# matts_pcb_schematic_v3.net
KiCad netlist of a schematic drawn in EAGLE
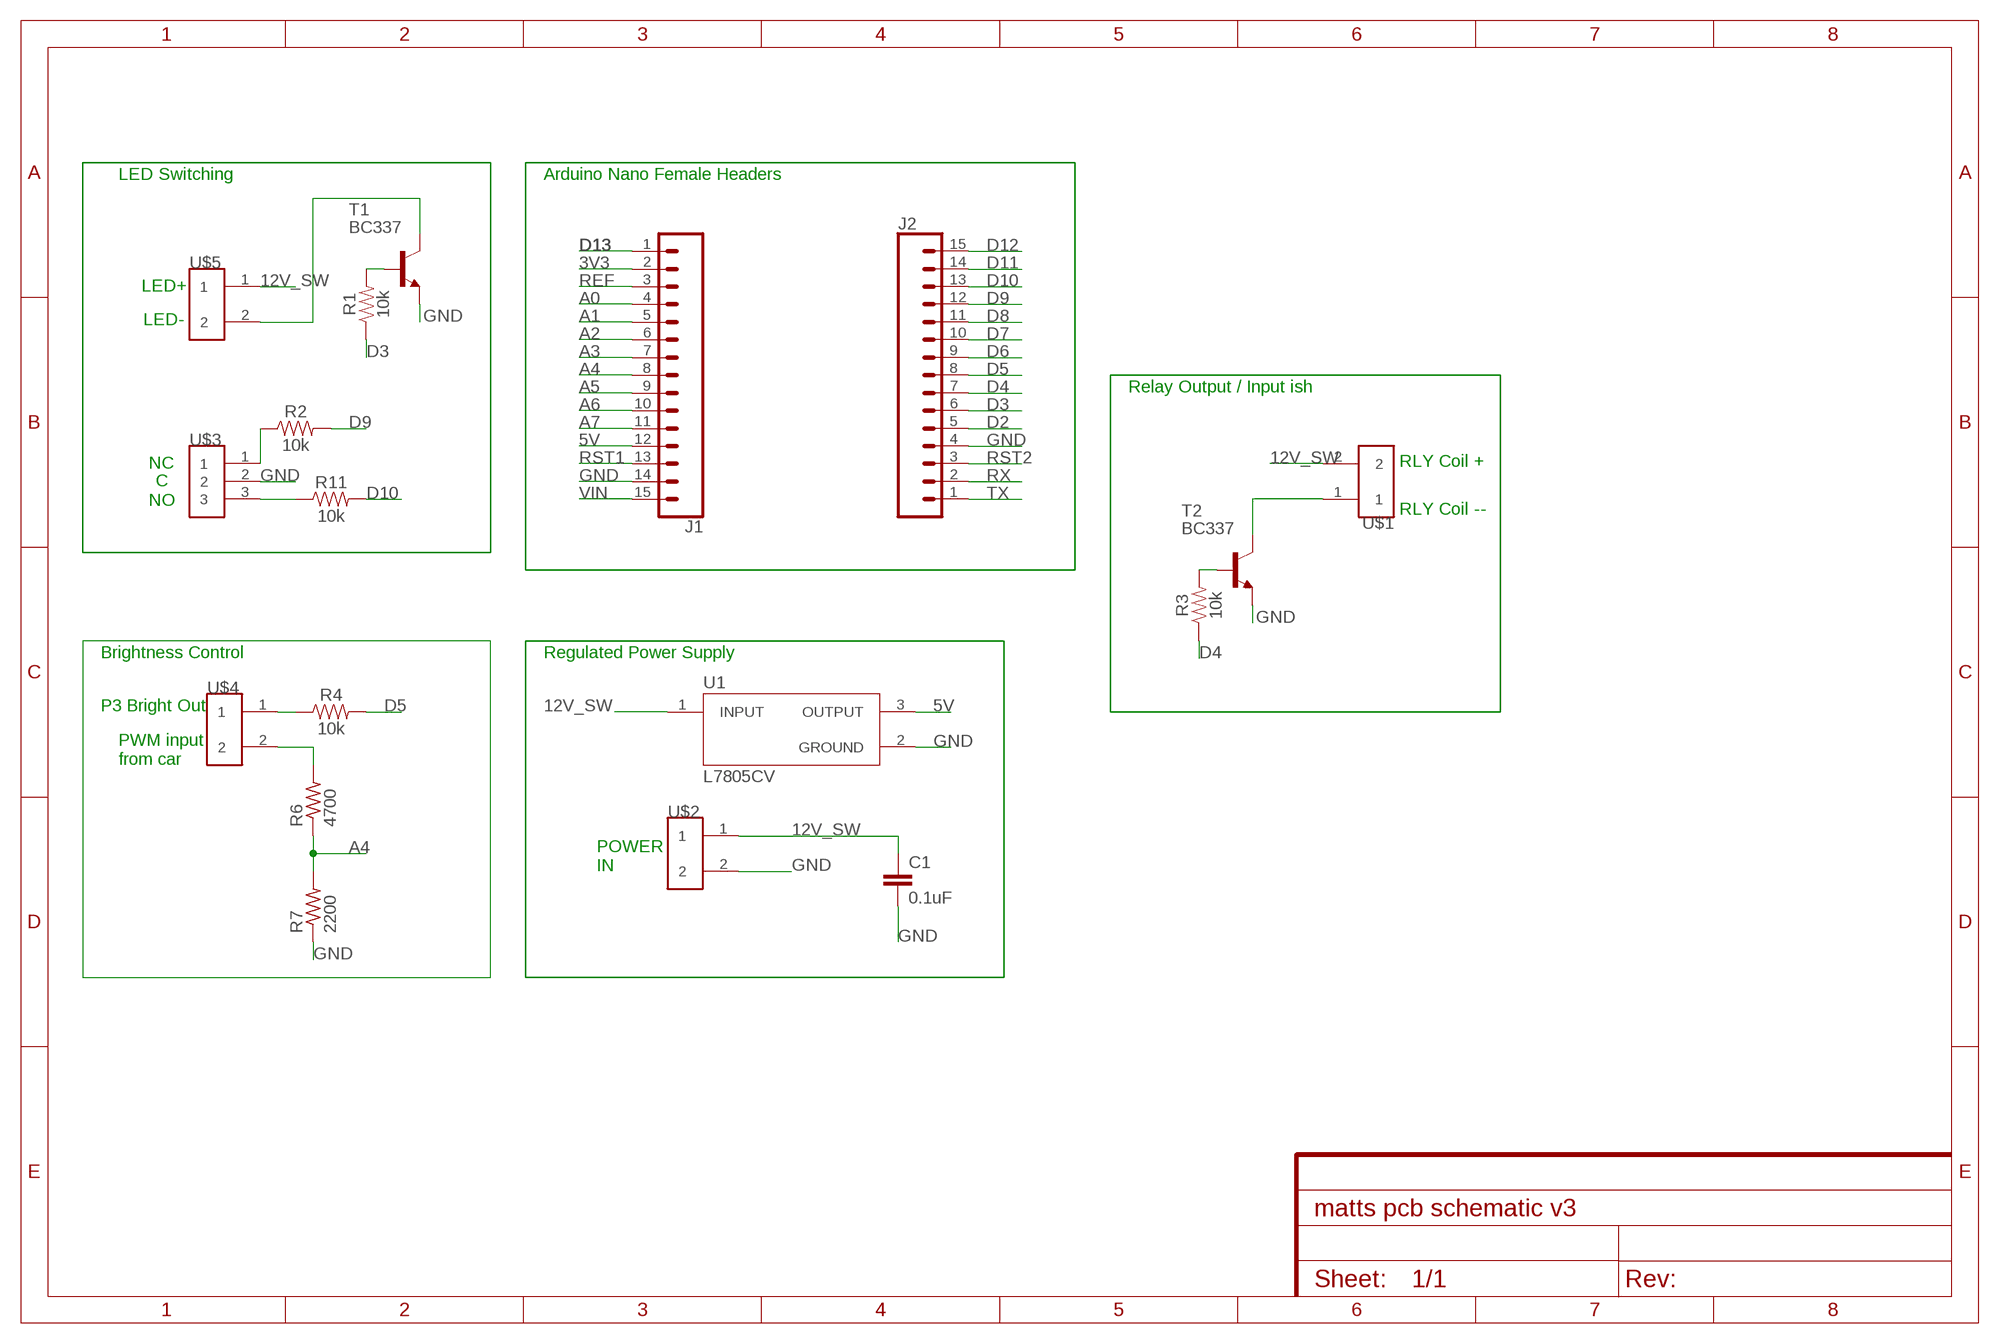
[diagram p0: schematic, sheet 1]

(export (version "E")
  (design (tool "Eeschema 10.0.6"))
  (components
    (comp (ref "C1")
      (value "0.1uF")
      (footprint "eagle-import:CAP-PTH-SMALL-KIT")
      (libsource (lib "eagle-import") (part "0.1UF-KIT-EZ-50V-20%"))
    )
    (comp (ref "J1")
      (value "CONN_15")
      (footprint "eagle-import:1X15")
      (libsource (lib "eagle-import") (part "CONN_15"))
    )
    (comp (ref "J2")
      (value "CONN_15")
      (footprint "eagle-import:1X15")
      (libsource (lib "eagle-import") (part "CONN_15"))
    )
    (comp (ref "R1")
      (value "10k")
      (footprint "eagle-import:AXIAL-0.3")
      (libsource (lib "eagle-import") (part "100KOHM-HORIZ-1/4W-1%"))
    )
    (comp (ref "R2")
      (value "10k")
      (footprint "eagle-import:AXIAL-0.3")
      (libsource (lib "eagle-import") (part "100KOHM-HORIZ-1/4W-1%"))
    )
    (comp (ref "R3")
      (value "10k")
      (footprint "eagle-import:AXIAL-0.3")
      (libsource (lib "eagle-import") (part "100KOHM-HORIZ-1/4W-1%"))
    )
    (comp (ref "R4")
      (value "10k")
      (footprint "eagle-import:AXIAL-0.3")
      (libsource (lib "eagle-import") (part "100KOHM-HORIZ-1/4W-1%"))
    )
    (comp (ref "R6")
      (value "4700")
      (footprint "eagle-import:0207_10")
      (libsource (lib "eagle-import") (part "R-US_0207/10"))
    )
    (comp (ref "R7")
      (value "2200")
      (footprint "eagle-import:0207_10")
      (libsource (lib "eagle-import") (part "R-US_0207/10"))
    )
    (comp (ref "R11")
      (value "10k")
      (footprint "eagle-import:AXIAL-0.3")
      (libsource (lib "eagle-import") (part "100KOHM-HORIZ-1/4W-1%"))
    )
    (comp (ref "T1")
      (value "BC337")
      (footprint "eagle-import:TO92")
      (libsource (lib "eagle-import") (part "BC337"))
    )
    (comp (ref "T2")
      (value "BC337")
      (footprint "eagle-import:TO92")
      (libsource (lib "eagle-import") (part "BC337"))
    )
    (comp (ref "U$1")
      (value "2PIN_0.2PITCH_SCREW_TERMINAL")
      (footprint "eagle-import:2PIN_0.2PITCH_SCREW_TERMINAL")
      (libsource (lib "eagle-import") (part "2PIN_0.2PITCH_SCREW_TERMINAL"))
    )
    (comp (ref "U$2")
      (value "2PIN_0.2PITCH_SCREW_TERMINAL")
      (footprint "eagle-import:2PIN_0.2PITCH_SCREW_TERMINAL")
      (libsource (lib "eagle-import") (part "2PIN_0.2PITCH_SCREW_TERMINAL"))
    )
    (comp (ref "U$3")
      (value "3PIN_0.2PITCH_SCREW_TERMINAL")
      (footprint "eagle-import:3PIN_0.2PITCH_SCREW_TERMINAL")
      (libsource (lib "eagle-import") (part "3PIN_0.2PITCH_SCREW_TERMINAL"))
    )
    (comp (ref "U$4")
      (value "2PIN_0.2PITCH_SCREW_TERMINAL")
      (footprint "eagle-import:2PIN_0.2PITCH_SCREW_TERMINAL")
      (libsource (lib "eagle-import") (part "2PIN_0.2PITCH_SCREW_TERMINAL"))
    )
    (comp (ref "U$5")
      (value "2PIN_0.2PITCH_SCREW_TERMINAL")
      (footprint "eagle-import:2PIN_0.2PITCH_SCREW_TERMINAL")
      (libsource (lib "eagle-import") (part "2PIN_0.2PITCH_SCREW_TERMINAL"))
    )
    (comp (ref "U1")
      (value "L7805CV")
      (footprint "eagle-import:TO255P1040X460X1968-3")
      (fields (field (name "MF") "STMicroelectronics"))
      (libsource (lib "eagle-import") (part "L7805CV"))
    )
  )
  (nets
    (net (code "1") (name "/3V3") (class "Default")
      (node (ref "J1") (pin "2") (pinfunction "2_2") (pintype "passive"))
    )
    (net (code "2") (name "/5V") (class "Default")
      (node (ref "J1") (pin "12") (pinfunction "12_12") (pintype "passive"))
      (node (ref "U1") (pin "3") (pinfunction "OUTPUT_3") (pintype "output"))
    )
    (net (code "3") (name "/12V_SW") (class "Default")
      (node (ref "C1") (pin "1") (pinfunction "1_1") (pintype "passive"))
      (node (ref "U$1") (pin "2") (pinfunction "2_2") (pintype "bidirectional"))
      (node (ref "U$2") (pin "1") (pinfunction "1_1") (pintype "bidirectional"))
      (node (ref "U$5") (pin "1") (pinfunction "1_1") (pintype "bidirectional"))
      (node (ref "U1") (pin "1") (pinfunction "INPUT_1") (pintype "input"))
    )
    (net (code "4") (name "/A0") (class "Default")
      (node (ref "J1") (pin "4") (pinfunction "4_4") (pintype "passive"))
    )
    (net (code "5") (name "/A1") (class "Default")
      (node (ref "J1") (pin "5") (pinfunction "5_5") (pintype "passive"))
    )
    (net (code "6") (name "/A2") (class "Default")
      (node (ref "J1") (pin "6") (pinfunction "6_6") (pintype "passive"))
    )
    (net (code "7") (name "/A3") (class "Default")
      (node (ref "J1") (pin "7") (pinfunction "7_7") (pintype "passive"))
    )
    (net (code "8") (name "/A4") (class "Default")
      (node (ref "J1") (pin "8") (pinfunction "8_8") (pintype "passive"))
      (node (ref "R6") (pin "1") (pinfunction "1_1") (pintype "passive"))
      (node (ref "R7") (pin "2") (pinfunction "2_2") (pintype "passive"))
    )
    (net (code "9") (name "/A5") (class "Default")
      (node (ref "J1") (pin "9") (pinfunction "9_9") (pintype "passive"))
    )
    (net (code "10") (name "/A6") (class "Default")
      (node (ref "J1") (pin "10") (pinfunction "10_10") (pintype "passive"))
    )
    (net (code "11") (name "/A7") (class "Default")
      (node (ref "J1") (pin "11") (pinfunction "11_11") (pintype "passive"))
    )
    (net (code "12") (name "/D2") (class "Default")
      (node (ref "J2") (pin "5") (pinfunction "5_5") (pintype "passive"))
    )
    (net (code "13") (name "/D3") (class "Default")
      (node (ref "J2") (pin "6") (pinfunction "6_6") (pintype "passive"))
      (node (ref "R1") (pin "P$1") (pinfunction "1_P$1") (pintype "passive"))
    )
    (net (code "14") (name "/D4") (class "Default")
      (node (ref "J2") (pin "7") (pinfunction "7_7") (pintype "passive"))
      (node (ref "R3") (pin "P$1") (pinfunction "1_P$1") (pintype "passive"))
    )
    (net (code "15") (name "/D5") (class "Default")
      (node (ref "J2") (pin "8") (pinfunction "8_8") (pintype "passive"))
      (node (ref "R4") (pin "P$2") (pinfunction "2_P$2") (pintype "passive"))
    )
    (net (code "16") (name "/D6") (class "Default")
      (node (ref "J2") (pin "9") (pinfunction "9_9") (pintype "passive"))
    )
    (net (code "17") (name "/D7") (class "Default")
      (node (ref "J2") (pin "10") (pinfunction "10_10") (pintype "passive"))
    )
    (net (code "18") (name "/D8") (class "Default")
      (node (ref "J2") (pin "11") (pinfunction "11_11") (pintype "passive"))
    )
    (net (code "19") (name "/D9") (class "Default")
      (node (ref "J2") (pin "12") (pinfunction "12_12") (pintype "passive"))
      (node (ref "R2") (pin "P$2") (pinfunction "2_P$2") (pintype "passive"))
    )
    (net (code "20") (name "/D10") (class "Default")
      (node (ref "J2") (pin "13") (pinfunction "13_13") (pintype "passive"))
      (node (ref "R11") (pin "P$2") (pinfunction "2_P$2") (pintype "passive"))
    )
    (net (code "21") (name "/D11") (class "Default")
      (node (ref "J2") (pin "14") (pinfunction "14_14") (pintype "passive"))
    )
    (net (code "22") (name "/D12") (class "Default")
      (node (ref "J2") (pin "15") (pinfunction "15_15") (pintype "passive"))
    )
    (net (code "23") (name "/D13") (class "Default")
      (node (ref "J1") (pin "1") (pinfunction "1_1") (pintype "passive"))
    )
    (net (code "24") (name "/GND") (class "Default")
      (node (ref "C1") (pin "2") (pinfunction "2_2") (pintype "passive"))
      (node (ref "J1") (pin "14") (pinfunction "14_14") (pintype "passive"))
      (node (ref "J2") (pin "4") (pinfunction "4_4") (pintype "passive"))
      (node (ref "R7") (pin "1") (pinfunction "1_1") (pintype "passive"))
      (node (ref "T1") (pin "1") (pinfunction "E_1") (pintype "passive"))
      (node (ref "T2") (pin "1") (pinfunction "E_1") (pintype "passive"))
      (node (ref "U$2") (pin "2") (pinfunction "2_2") (pintype "bidirectional"))
      (node (ref "U$3") (pin "2") (pinfunction "2_2") (pintype "bidirectional"))
      (node (ref "U1") (pin "2") (pinfunction "GROUND_2") (pintype "power_in"))
    )
    (net (code "25") (name "/REF") (class "Default")
      (node (ref "J1") (pin "3") (pinfunction "3_3") (pintype "passive"))
    )
    (net (code "26") (name "/RST1") (class "Default")
      (node (ref "J1") (pin "13") (pinfunction "13_13") (pintype "passive"))
    )
    (net (code "27") (name "/RST2") (class "Default")
      (node (ref "J2") (pin "3") (pinfunction "3_3") (pintype "passive"))
    )
    (net (code "28") (name "/RX") (class "Default")
      (node (ref "J2") (pin "2") (pinfunction "2_2") (pintype "passive"))
    )
    (net (code "29") (name "/TX") (class "Default")
      (node (ref "J2") (pin "1") (pinfunction "1_1") (pintype "passive"))
    )
    (net (code "30") (name "/VIN") (class "Default")
      (node (ref "J1") (pin "15") (pinfunction "15_15") (pintype "passive"))
    )
    (net (code "31") (name "Net-(R1-2)") (class "Default")
      (node (ref "R1") (pin "P$2") (pinfunction "2_P$2") (pintype "passive"))
      (node (ref "T1") (pin "2") (pinfunction "B_2") (pintype "passive"))
    )
    (net (code "32") (name "Net-(R2-1)") (class "Default")
      (node (ref "R2") (pin "P$1") (pinfunction "1_P$1") (pintype "passive"))
      (node (ref "U$3") (pin "1") (pinfunction "1_1") (pintype "bidirectional"))
    )
    (net (code "33") (name "Net-(R3-2)") (class "Default")
      (node (ref "R3") (pin "P$2") (pinfunction "2_P$2") (pintype "passive"))
      (node (ref "T2") (pin "2") (pinfunction "B_2") (pintype "passive"))
    )
    (net (code "34") (name "Net-(R4-1)") (class "Default")
      (node (ref "R4") (pin "P$1") (pinfunction "1_P$1") (pintype "passive"))
      (node (ref "U$4") (pin "1") (pinfunction "1_1") (pintype "bidirectional"))
    )
    (net (code "35") (name "Net-(R6-Pad2)") (class "Default")
      (node (ref "R6") (pin "2") (pinfunction "2_2") (pintype "passive"))
      (node (ref "U$4") (pin "2") (pinfunction "2_2") (pintype "bidirectional"))
    )
    (net (code "36") (name "Net-(R11-1)") (class "Default")
      (node (ref "R11") (pin "P$1") (pinfunction "1_P$1") (pintype "passive"))
      (node (ref "U$3") (pin "3") (pinfunction "3_3") (pintype "bidirectional"))
    )
    (net (code "37") (name "Net-(T1-C)") (class "Default")
      (node (ref "T1") (pin "3") (pinfunction "C_3") (pintype "passive"))
      (node (ref "U$5") (pin "2") (pinfunction "2_2") (pintype "bidirectional"))
    )
    (net (code "38") (name "Net-(T2-C)") (class "Default")
      (node (ref "T2") (pin "3") (pinfunction "C_3") (pintype "passive"))
      (node (ref "U$1") (pin "1") (pinfunction "1_1") (pintype "bidirectional"))
    )
  )
)
